# rotary_encoder_3.net
KiCad netlist of a schematic drawn in EAGLE
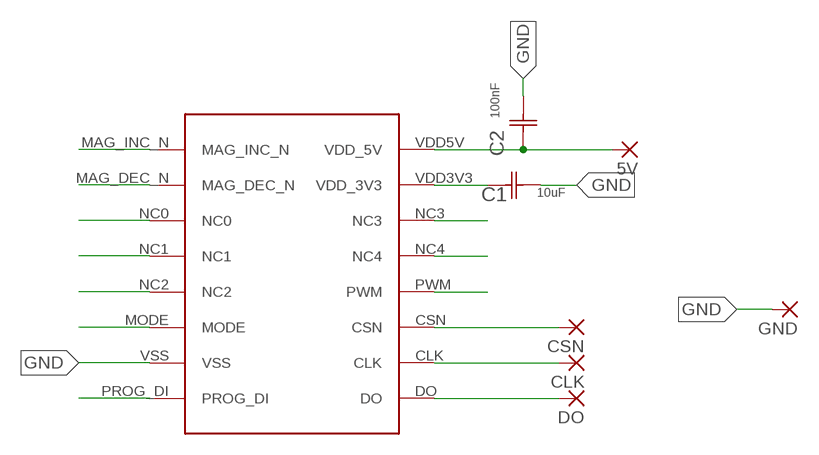
[diagram p0: schematic, sheet 1]

(export (version "E")
  (design (tool "Eeschema 10.0.6"))
  (components
    (comp (ref "5V")
      (value "1,6/0,8")
      (footprint "eagle-import:1,6_0,8")
      (libsource (lib "eagle-import") (part "1,6/0,8"))
    )
    (comp (ref "C1")
      (value "10uF")
      (footprint "eagle-import:CAP_0805_100NF")
      (fields (field (name "MPN") "0805F106Z100CT") (field (name "TOLERANCE") "-20/+80%"))
      (libsource (lib "eagle-import") (part "CAP_0805_10UF"))
    )
    (comp (ref "C2")
      (value "100nF")
      (footprint "eagle-import:CAP_0805_100NF")
      (fields (field (name "MPN") "U0805F104ZCT") (field (name "TOLERANCE") "-20/+80%"))
      (libsource (lib "eagle-import") (part "CAP_0805_100NF"))
    )
    (comp (ref "CLK")
      (value "1,6/0,8")
      (footprint "eagle-import:1,6_0,8")
      (libsource (lib "eagle-import") (part "1,6/0,8"))
    )
    (comp (ref "CSN")
      (value "1,6/0,8")
      (footprint "eagle-import:1,6_0,8")
      (libsource (lib "eagle-import") (part "1,6/0,8"))
    )
    (comp (ref "DO")
      (value "1,6/0,8")
      (footprint "eagle-import:1,6_0,8")
      (libsource (lib "eagle-import") (part "1,6/0,8"))
    )
    (comp (ref "GND")
      (value "1,6/0,8")
      (footprint "eagle-import:1,6_0,8")
      (libsource (lib "eagle-import") (part "1,6/0,8"))
    )
    (comp (ref "U$1")
      (value "AS5045_ROTARY_ENCODER")
      (footprint "eagle-import:AS5045_ROTARY_ENCODER")
      (libsource (lib "eagle-import") (part "AS5045_ROTARY_ENCODER"))
    )
  )
  (nets
    (net (code "1") (name "GND") (class "Default")
      (node (ref "C1") (pin "2") (pinfunction "C2_2") (pintype "passive"))
      (node (ref "C2") (pin "2") (pinfunction "C2_2") (pintype "passive"))
      (node (ref "GND") (pin "1") (pinfunction "P_1") (pintype "passive"))
      (node (ref "U$1") (pin "VSS") (pinfunction "VSS_VSS") (pintype "bidirectional"))
    )
    (net (code "2") (name "Net-(5V-P)") (class "Default")
      (node (ref "5V") (pin "1") (pinfunction "P_1") (pintype "passive"))
      (node (ref "C2") (pin "1") (pinfunction "C1_1") (pintype "passive"))
      (node (ref "U$1") (pin "VDD5V") (pinfunction "VDD_5V_VDD5V") (pintype "bidirectional"))
    )
    (net (code "3") (name "Net-(C1-C1)") (class "Default")
      (node (ref "C1") (pin "1") (pinfunction "C1_1") (pintype "passive"))
      (node (ref "U$1") (pin "VDD3V3") (pinfunction "VDD_3V3_VDD3V3") (pintype "bidirectional"))
    )
    (net (code "4") (name "Net-(CLK-P)") (class "Default")
      (node (ref "CLK") (pin "1") (pinfunction "P_1") (pintype "passive"))
      (node (ref "U$1") (pin "CLK") (pinfunction "CLK_CLK") (pintype "bidirectional"))
    )
    (net (code "5") (name "Net-(CSN-P)") (class "Default")
      (node (ref "CSN") (pin "1") (pinfunction "P_1") (pintype "passive"))
      (node (ref "U$1") (pin "CSN") (pinfunction "CSN_CSN") (pintype "bidirectional"))
    )
    (net (code "6") (name "Net-(DO-P)") (class "Default")
      (node (ref "DO") (pin "1") (pinfunction "P_1") (pintype "passive"))
      (node (ref "U$1") (pin "DO") (pinfunction "DO_DO") (pintype "bidirectional"))
    )
    (net (code "7") (name "unconnected-(U$1-PadMAG_DEC_N)") (class "Default")
      (node (ref "U$1") (pin "MAG_DEC_N") (pinfunction "MAG_DEC_N_MAG_DEC_N") (pintype "bidirectional"))
    )
    (net (code "8") (name "unconnected-(U$1-PadMAG_INC_N)") (class "Default")
      (node (ref "U$1") (pin "MAG_INC_N") (pinfunction "MAG_INC_N_MAG_INC_N") (pintype "bidirectional"))
    )
    (net (code "9") (name "unconnected-(U$1-PadMODE)") (class "Default")
      (node (ref "U$1") (pin "MODE") (pinfunction "MODE_MODE") (pintype "bidirectional"))
    )
    (net (code "10") (name "unconnected-(U$1-PadNC0)") (class "Default")
      (node (ref "U$1") (pin "NC0") (pinfunction "NC0_NC0") (pintype "bidirectional"))
    )
    (net (code "11") (name "unconnected-(U$1-PadNC1)") (class "Default")
      (node (ref "U$1") (pin "NC1") (pinfunction "NC1_NC1") (pintype "bidirectional"))
    )
    (net (code "12") (name "unconnected-(U$1-PadNC2)") (class "Default")
      (node (ref "U$1") (pin "NC2") (pinfunction "NC2_NC2") (pintype "bidirectional"))
    )
    (net (code "13") (name "unconnected-(U$1-PadNC3)") (class "Default")
      (node (ref "U$1") (pin "NC3") (pinfunction "NC3_NC3") (pintype "bidirectional"))
    )
    (net (code "14") (name "unconnected-(U$1-PadNC4)") (class "Default")
      (node (ref "U$1") (pin "NC4") (pinfunction "NC4_NC4") (pintype "bidirectional"))
    )
    (net (code "15") (name "unconnected-(U$1-PadPROG_DI)") (class "Default")
      (node (ref "U$1") (pin "PROG_DI") (pinfunction "PROG_DI_PROG_DI") (pintype "bidirectional"))
    )
    (net (code "16") (name "unconnected-(U$1-PadPWM)") (class "Default")
      (node (ref "U$1") (pin "PWM") (pinfunction "PWM_PWM") (pintype "bidirectional"))
    )
  )
)
